# LCDTFT_CTRL_FT800.net
KiCad netlist of a schematic drawn in Altium Designer
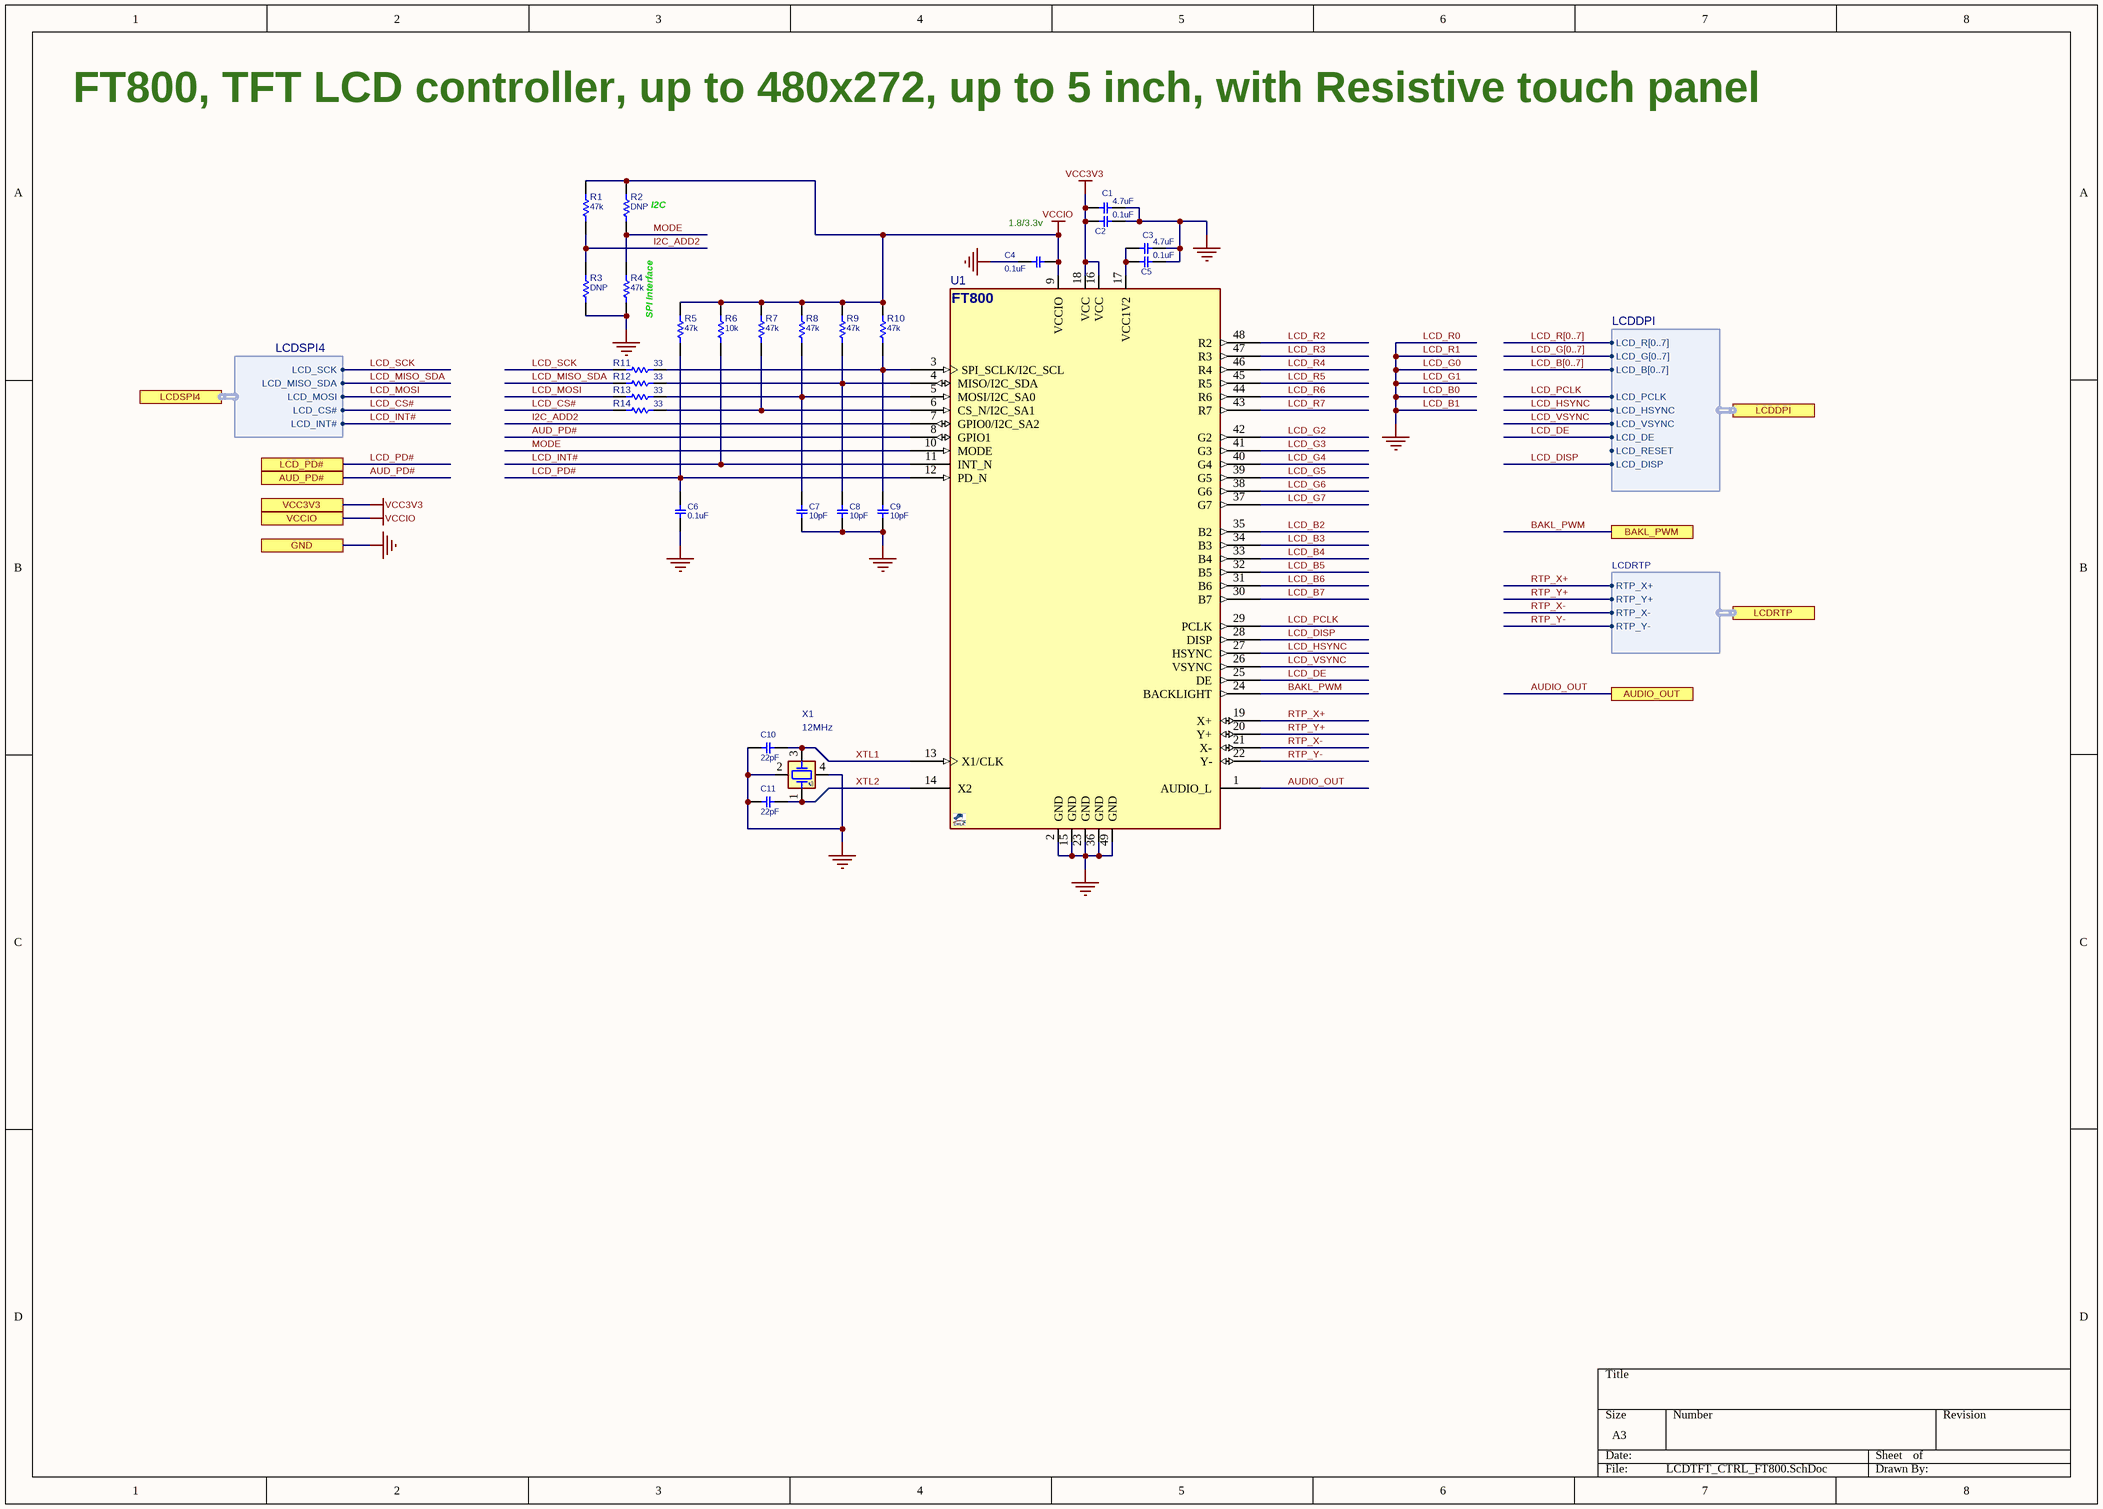
[diagram p0: LCDTFT_CTRL_FT800.SchDoc]

(export (version "E")
  (design (tool "Eeschema 10.0.6"))
  (components
    (comp (ref "C1")
      (value "4.7uF")
      (footprint "C0603")
      (description "CAP, MLCC")
      (libsource (lib "passive_smd") (part "CAP_SMD_MLCC"))
    )
    (comp (ref "C2")
      (value "0.1uF")
      (footprint "C0402")
      (description "CAP, MLCC")
      (fields (field (name "MANF_P#") "GRM155R71H104KE14D") (field (name "MANF") "Murata"))
      (libsource (lib "passive_smd") (part "CAP_SMD_MLCC"))
    )
    (comp (ref "C3")
      (value "4.7uF")
      (footprint "C0603")
      (description "CAP, MLCC")
      (libsource (lib "passive_smd") (part "CAP_SMD_MLCC"))
    )
    (comp (ref "C4")
      (value "0.1uF")
      (footprint "C0402")
      (description "CAP, MLCC")
      (fields (field (name "MANF_P#") "GRM155R71H104KE14D") (field (name "MANF") "Murata"))
      (libsource (lib "passive_smd") (part "CAP_SMD_MLCC"))
    )
    (comp (ref "C5")
      (value "0.1uF")
      (footprint "C0402")
      (description "CAP, MLCC")
      (fields (field (name "MANF_P#") "GRM155R71H104KE14D") (field (name "MANF") "Murata"))
      (libsource (lib "passive_smd") (part "CAP_SMD_MLCC"))
    )
    (comp (ref "C6")
      (value "0.1uF")
      (footprint "C0402")
      (description "CAP, MLCC")
      (fields (field (name "MANF_P#") "GRM155R71H104KE14D") (field (name "MANF") "Murata"))
      (libsource (lib "passive_smd") (part "CAP_SMD_MLCC"))
    )
    (comp (ref "C7")
      (value "10pF")
      (footprint "C0402")
      (description "CAP, MLCC")
      (libsource (lib "passive_smd") (part "CAP_SMD_MLCC"))
    )
    (comp (ref "C8")
      (value "10pF")
      (footprint "C0402")
      (description "CAP, MLCC")
      (libsource (lib "passive_smd") (part "CAP_SMD_MLCC"))
    )
    (comp (ref "C9")
      (value "10pF")
      (footprint "C0402")
      (description "CAP, MLCC")
      (libsource (lib "passive_smd") (part "CAP_SMD_MLCC"))
    )
    (comp (ref "C10")
      (value "22pF")
      (footprint "C0402")
      (description "CAP, MLCC")
      (libsource (lib "passive_smd") (part "CAP_SMD_MLCC"))
    )
    (comp (ref "C11")
      (value "22pF")
      (footprint "C0402")
      (description "CAP, MLCC")
      (libsource (lib "passive_smd") (part "CAP_SMD_MLCC"))
    )
    (comp (ref "R1")
      (value "47k")
      (footprint "R0402")
      (description "RESISTOR, SMD")
      (libsource (lib "passive_res_smd") (part "RES_SMD"))
    )
    (comp (ref "R2")
      (value "DNP")
      (footprint "R0402")
      (description "RESISTOR, SMD")
      (libsource (lib "passive_res_smd") (part "RES_SMD"))
    )
    (comp (ref "R3")
      (value "DNP")
      (footprint "R0402")
      (description "RESISTOR, SMD")
      (libsource (lib "passive_res_smd") (part "RES_SMD"))
    )
    (comp (ref "R4")
      (value "47k")
      (footprint "R0402")
      (description "RESISTOR, SMD")
      (libsource (lib "passive_res_smd") (part "RES_SMD"))
    )
    (comp (ref "R5")
      (value "47k")
      (footprint "R0402")
      (description "RESISTOR, SMD")
      (libsource (lib "passive_res_smd") (part "RES_SMD"))
    )
    (comp (ref "R6")
      (value "10k")
      (footprint "R0402")
      (description "RESISTOR, SMD")
      (libsource (lib "passive_res_smd") (part "RES_SMD"))
    )
    (comp (ref "R7")
      (value "47k")
      (footprint "R0402")
      (description "RESISTOR, SMD")
      (libsource (lib "passive_res_smd") (part "RES_SMD"))
    )
    (comp (ref "R8")
      (value "47k")
      (footprint "R0402")
      (description "RESISTOR, SMD")
      (libsource (lib "passive_res_smd") (part "RES_SMD"))
    )
    (comp (ref "R9")
      (value "47k")
      (footprint "R0402")
      (description "RESISTOR, SMD")
      (libsource (lib "passive_res_smd") (part "RES_SMD"))
    )
    (comp (ref "R10")
      (value "47k")
      (footprint "R0402")
      (description "RESISTOR, SMD")
      (libsource (lib "passive_res_smd") (part "RES_SMD"))
    )
    (comp (ref "R11")
      (value "33")
      (footprint "R0402")
      (description "RESISTOR, SMD")
      (libsource (lib "passive_res_smd") (part "RES_SMD"))
    )
    (comp (ref "R12")
      (value "33")
      (footprint "R0402")
      (description "RESISTOR, SMD")
      (libsource (lib "passive_res_smd") (part "RES_SMD"))
    )
    (comp (ref "R13")
      (value "33")
      (footprint "R0402")
      (description "RESISTOR, SMD")
      (libsource (lib "passive_res_smd") (part "RES_SMD"))
    )
    (comp (ref "R14")
      (value "33")
      (footprint "R0402")
      (description "RESISTOR, SMD")
      (libsource (lib "passive_res_smd") (part "RES_SMD"))
    )
    (comp (ref "U1")
      (value "FT800")
      (footprint "QFN50_48T")
      (description "LCD Display Controller, Embedded Video Engine, QFN-48")
      (fields (field (name "MANF") "FTDI/Bridgetek") (field (name "MANF_P#") "FT800Q"))
      (libsource (lib "lcdtft_controller") (part "FT800_QFN48"))
    )
    (comp (ref "X1")
      (value "12MHz")
      (footprint "XTL_4_3225")
      (description "Crystal 12MHz")
      (fields (field (name "MANF") "ECS") (field (name "MANF_P#") "ECS-120-18-33-JEM-TR"))
      (libsource (lib "crystal") (part "XTL_4_12MHz_3225"))
    )
  )
  (nets
    (net (code "4") (name "/AUDIO_OUT") (class "Default")
      (node (ref "U1") (pin "1") (pinfunction "AUDIO_L_1") (pintype "tri_state"))
    )
    (net (code "5") (name "/AUD_PD#") (class "Default")
      (node (ref "U1") (pin "8") (pinfunction "GPIO1_8") (pintype "bidirectional"))
    )
    (net (code "6") (name "/BAKL_PWM") (class "Default")
      (node (ref "U1") (pin "24") (pinfunction "BACKLIGHT_24") (pintype "output"))
    )
    (net (code "7") (name "/I2C_ADD2") (class "Default")
      (node (ref "R1") (pin "2") (pinfunction "2_2") (pintype "passive"))
      (node (ref "R3") (pin "1") (pinfunction "1_1") (pintype "passive"))
      (node (ref "U1") (pin "7") (pinfunction "GPIO0/I2C_SA2_7") (pintype "bidirectional"))
    )
    (net (code "8") (name "/LCD_B2") (class "Default")
      (node (ref "U1") (pin "35") (pinfunction "B2_35") (pintype "output"))
    )
    (net (code "9") (name "/LCD_B3") (class "Default")
      (node (ref "U1") (pin "34") (pinfunction "B3_34") (pintype "output"))
    )
    (net (code "10") (name "/LCD_B4") (class "Default")
      (node (ref "U1") (pin "33") (pinfunction "B4_33") (pintype "output"))
    )
    (net (code "11") (name "/LCD_B5") (class "Default")
      (node (ref "U1") (pin "32") (pinfunction "B5_32") (pintype "output"))
    )
    (net (code "12") (name "/LCD_B6") (class "Default")
      (node (ref "U1") (pin "31") (pinfunction "B6_31") (pintype "output"))
    )
    (net (code "13") (name "/LCD_B7") (class "Default")
      (node (ref "U1") (pin "30") (pinfunction "B7_30") (pintype "output"))
    )
    (net (code "15") (name "/LCD_CS#") (class "Default")
      (node (ref "R14") (pin "1") (pinfunction "1_1") (pintype "passive"))
    )
    (net (code "16") (name "/LCD_DE") (class "Default")
      (node (ref "U1") (pin "25") (pinfunction "DE_25") (pintype "output"))
    )
    (net (code "17") (name "/LCD_DISP") (class "Default")
      (node (ref "U1") (pin "28") (pinfunction "DISP_28") (pintype "output"))
    )
    (net (code "18") (name "/LCD_G2") (class "Default")
      (node (ref "U1") (pin "42") (pinfunction "G2_42") (pintype "output"))
    )
    (net (code "19") (name "/LCD_G3") (class "Default")
      (node (ref "U1") (pin "41") (pinfunction "G3_41") (pintype "output"))
    )
    (net (code "20") (name "/LCD_G4") (class "Default")
      (node (ref "U1") (pin "40") (pinfunction "G4_40") (pintype "output"))
    )
    (net (code "21") (name "/LCD_G5") (class "Default")
      (node (ref "U1") (pin "39") (pinfunction "G5_39") (pintype "output"))
    )
    (net (code "22") (name "/LCD_G6") (class "Default")
      (node (ref "U1") (pin "38") (pinfunction "G6_38") (pintype "output"))
    )
    (net (code "23") (name "/LCD_G7") (class "Default")
      (node (ref "U1") (pin "37") (pinfunction "G7_37") (pintype "output"))
    )
    (net (code "25") (name "/LCD_HSYNC") (class "Default")
      (node (ref "U1") (pin "27") (pinfunction "HSYNC_27") (pintype "output"))
    )
    (net (code "26") (name "/LCD_INT#") (class "Default")
      (node (ref "R6") (pin "2") (pinfunction "2_2") (pintype "passive"))
      (node (ref "U1") (pin "11") (pinfunction "INT_N_11") (pintype "tri_state"))
    )
    (net (code "27") (name "/LCD_MISO_SDA") (class "Default")
      (node (ref "R12") (pin "1") (pinfunction "1_1") (pintype "passive"))
    )
    (net (code "28") (name "/LCD_MOSI") (class "Default")
      (node (ref "R13") (pin "1") (pinfunction "1_1") (pintype "passive"))
    )
    (net (code "29") (name "/LCD_PCLK") (class "Default")
      (node (ref "U1") (pin "29") (pinfunction "PCLK_29") (pintype "output"))
    )
    (net (code "30") (name "/LCD_PD#") (class "Default")
      (node (ref "C6") (pin "1") (pinfunction "1_1") (pintype "passive"))
      (node (ref "R5") (pin "2") (pinfunction "2_2") (pintype "passive"))
      (node (ref "U1") (pin "12") (pinfunction "PD_N_12") (pintype "input"))
    )
    (net (code "31") (name "/LCD_R2") (class "Default")
      (node (ref "U1") (pin "48") (pinfunction "R2_48") (pintype "output"))
    )
    (net (code "32") (name "/LCD_R3") (class "Default")
      (node (ref "U1") (pin "47") (pinfunction "R3_47") (pintype "output"))
    )
    (net (code "33") (name "/LCD_R4") (class "Default")
      (node (ref "U1") (pin "46") (pinfunction "R4_46") (pintype "output"))
    )
    (net (code "34") (name "/LCD_R5") (class "Default")
      (node (ref "U1") (pin "45") (pinfunction "R5_45") (pintype "output"))
    )
    (net (code "35") (name "/LCD_R6") (class "Default")
      (node (ref "U1") (pin "44") (pinfunction "R6_44") (pintype "output"))
    )
    (net (code "36") (name "/LCD_R7") (class "Default")
      (node (ref "U1") (pin "43") (pinfunction "R7_43") (pintype "output"))
    )
    (net (code "38") (name "/LCD_SCK") (class "Default")
      (node (ref "R11") (pin "1") (pinfunction "1_1") (pintype "passive"))
    )
    (net (code "39") (name "/LCD_VSYNC") (class "Default")
      (node (ref "U1") (pin "26") (pinfunction "VSYNC_26") (pintype "output"))
    )
    (net (code "40") (name "/MODE") (class "Default")
      (node (ref "R2") (pin "2") (pinfunction "2_2") (pintype "passive"))
      (node (ref "R4") (pin "1") (pinfunction "1_1") (pintype "passive"))
      (node (ref "U1") (pin "10") (pinfunction "MODE_10") (pintype "input"))
    )
    (net (code "41") (name "/RTP_X+") (class "Default")
      (node (ref "U1") (pin "19") (pinfunction "X+_19") (pintype "bidirectional"))
    )
    (net (code "42") (name "/RTP_X-") (class "Default")
      (node (ref "U1") (pin "21") (pinfunction "X-_21") (pintype "bidirectional"))
    )
    (net (code "43") (name "/RTP_Y+") (class "Default")
      (node (ref "U1") (pin "20") (pinfunction "Y+_20") (pintype "bidirectional"))
    )
    (net (code "44") (name "/RTP_Y-") (class "Default")
      (node (ref "U1") (pin "22") (pinfunction "Y-_22") (pintype "bidirectional"))
    )
    (net (code "45") (name "/XTL1") (class "Default")
      (node (ref "C10") (pin "2") (pinfunction "2_2") (pintype "passive"))
      (node (ref "U1") (pin "13") (pinfunction "X1/CLK_13") (pintype "input"))
      (node (ref "X1") (pin "3") (pinfunction "2_3") (pintype "passive"))
    )
    (net (code "46") (name "/XTL2") (class "Default")
      (node (ref "C11") (pin "1") (pinfunction "1_1") (pintype "passive"))
      (node (ref "U1") (pin "14") (pinfunction "X2_14") (pintype "passive"))
      (node (ref "X1") (pin "1") (pinfunction "1_1") (pintype "passive"))
    )
    (net (code "50") (name "GND") (class "Default")
      (node (ref "C1") (pin "1") (pinfunction "1_1") (pintype "passive"))
      (node (ref "C10") (pin "1") (pinfunction "1_1") (pintype "passive"))
      (node (ref "C11") (pin "2") (pinfunction "2_2") (pintype "passive"))
      (node (ref "C2") (pin "1") (pinfunction "1_1") (pintype "passive"))
      (node (ref "C3") (pin "1") (pinfunction "1_1") (pintype "passive"))
      (node (ref "C4") (pin "2") (pinfunction "2_2") (pintype "passive"))
      (node (ref "C5") (pin "1") (pinfunction "1_1") (pintype "passive"))
      (node (ref "C6") (pin "2") (pinfunction "2_2") (pintype "passive"))
      (node (ref "C7") (pin "2") (pinfunction "2_2") (pintype "passive"))
      (node (ref "C8") (pin "2") (pinfunction "2_2") (pintype "passive"))
      (node (ref "C9") (pin "2") (pinfunction "2_2") (pintype "passive"))
      (node (ref "R3") (pin "2") (pinfunction "2_2") (pintype "passive"))
      (node (ref "R4") (pin "2") (pinfunction "2_2") (pintype "passive"))
      (node (ref "U1") (pin "15") (pinfunction "GND_15") (pintype "power_in"))
      (node (ref "U1") (pin "2") (pinfunction "GND_2") (pintype "power_in"))
      (node (ref "U1") (pin "23") (pinfunction "GND_23") (pintype "power_in"))
      (node (ref "U1") (pin "36") (pinfunction "GND_36") (pintype "power_in"))
      (node (ref "U1") (pin "49") (pinfunction "GND_49") (pintype "power_in"))
      (node (ref "X1") (pin "2") (pinfunction "2_2") (pintype "passive"))
      (node (ref "X1") (pin "4") (pinfunction "4_4") (pintype "passive"))
    )
    (net (code "51") (name "Net-(U1-CS_N{slash}I2C_SA1)") (class "Default")
      (node (ref "R14") (pin "2") (pinfunction "2_2") (pintype "passive"))
      (node (ref "R7") (pin "2") (pinfunction "2_2") (pintype "passive"))
      (node (ref "U1") (pin "6") (pinfunction "CS_N/I2C_SA1_6") (pintype "input"))
    )
    (net (code "52") (name "Net-(U1-MISO{slash}I2C_SDA)") (class "Default")
      (node (ref "C8") (pin "1") (pinfunction "1_1") (pintype "passive"))
      (node (ref "R12") (pin "2") (pinfunction "2_2") (pintype "passive"))
      (node (ref "R9") (pin "2") (pinfunction "2_2") (pintype "passive"))
      (node (ref "U1") (pin "4") (pinfunction "MISO/I2C_SDA_4") (pintype "bidirectional"))
    )
    (net (code "53") (name "Net-(U1-MOSI{slash}I2C_SA0)") (class "Default")
      (node (ref "C7") (pin "1") (pinfunction "1_1") (pintype "passive"))
      (node (ref "R13") (pin "2") (pinfunction "2_2") (pintype "passive"))
      (node (ref "R8") (pin "2") (pinfunction "2_2") (pintype "passive"))
      (node (ref "U1") (pin "5") (pinfunction "MOSI/I2C_SA0_5") (pintype "input"))
    )
    (net (code "54") (name "Net-(U1-SPI_SCLK{slash}I2C_SCL)") (class "Default")
      (node (ref "C9") (pin "1") (pinfunction "1_1") (pintype "passive"))
      (node (ref "R10") (pin "2") (pinfunction "2_2") (pintype "passive"))
      (node (ref "R11") (pin "2") (pinfunction "2_2") (pintype "passive"))
      (node (ref "U1") (pin "3") (pinfunction "SPI_SCLK/I2C_SCL_3") (pintype "input"))
    )
    (net (code "55") (name "Net-(U1-VCC1V2)") (class "Default")
      (node (ref "C3") (pin "2") (pinfunction "2_2") (pintype "passive"))
      (node (ref "C5") (pin "2") (pinfunction "2_2") (pintype "passive"))
      (node (ref "U1") (pin "17") (pinfunction "VCC1V2_17") (pintype "power_in"))
    )
    (net (code "56") (name "VCC3V3") (class "Default")
      (node (ref "C1") (pin "2") (pinfunction "2_2") (pintype "passive"))
      (node (ref "C2") (pin "2") (pinfunction "2_2") (pintype "passive"))
      (node (ref "U1") (pin "16") (pinfunction "VCC_16") (pintype "power_in"))
      (node (ref "U1") (pin "18") (pinfunction "VCC_18") (pintype "power_in"))
    )
    (net (code "57") (name "VCCIO") (class "Default")
      (node (ref "C4") (pin "1") (pinfunction "1_1") (pintype "passive"))
      (node (ref "R1") (pin "1") (pinfunction "1_1") (pintype "passive"))
      (node (ref "R10") (pin "1") (pinfunction "1_1") (pintype "passive"))
      (node (ref "R2") (pin "1") (pinfunction "1_1") (pintype "passive"))
      (node (ref "R5") (pin "1") (pinfunction "1_1") (pintype "passive"))
      (node (ref "R6") (pin "1") (pinfunction "1_1") (pintype "passive"))
      (node (ref "R7") (pin "1") (pinfunction "1_1") (pintype "passive"))
      (node (ref "R8") (pin "1") (pinfunction "1_1") (pintype "passive"))
      (node (ref "R9") (pin "1") (pinfunction "1_1") (pintype "passive"))
      (node (ref "U1") (pin "9") (pinfunction "VCCIO_9") (pintype "power_in"))
    )
  )
)
